# BMS.net
KiCad netlist of a schematic drawn in Altium Designer
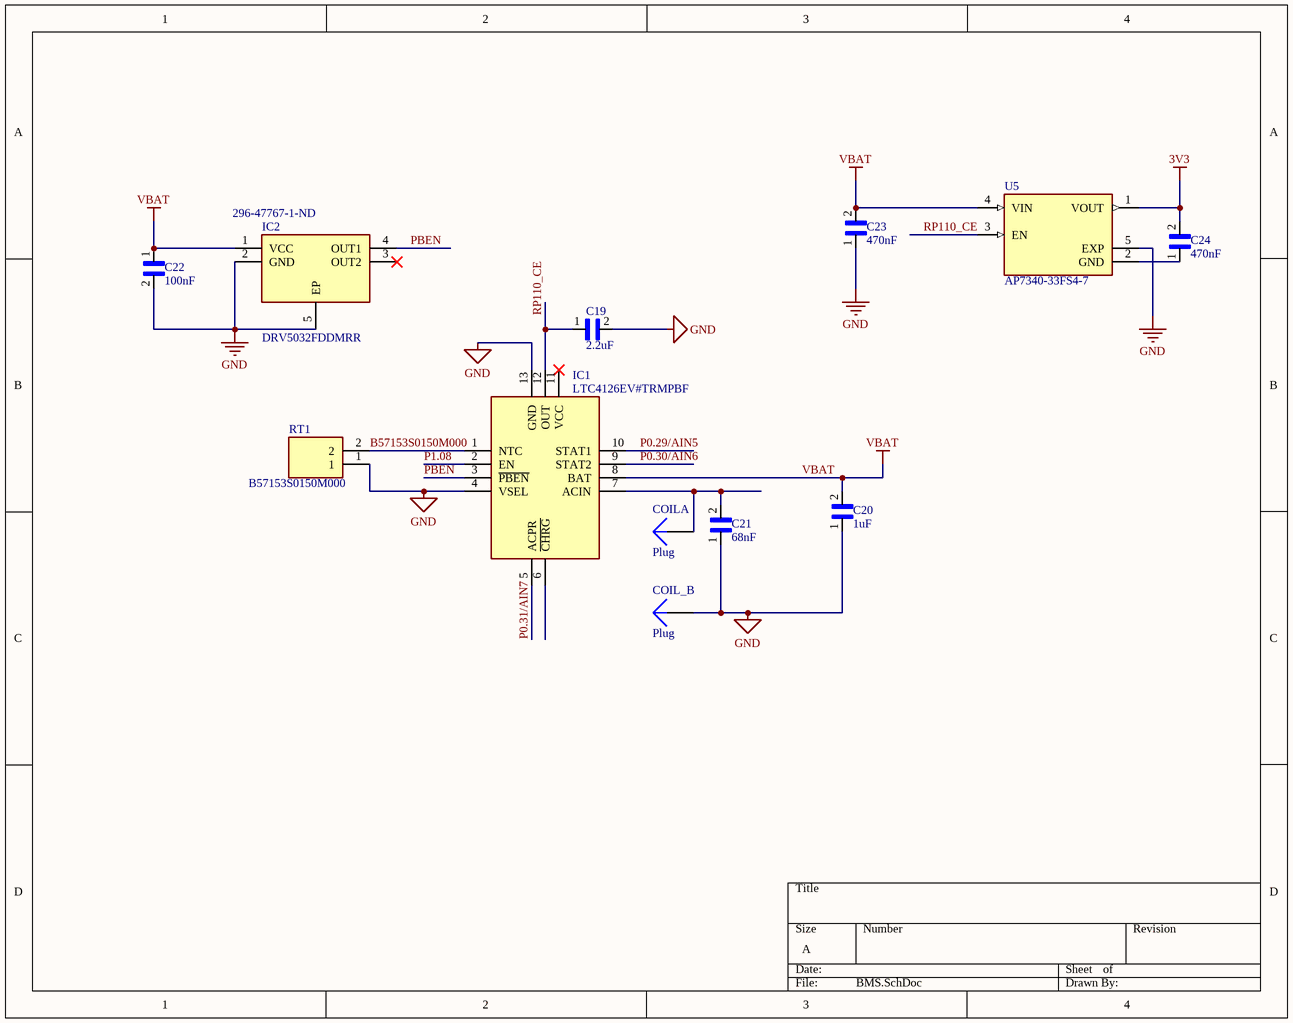
[diagram p0: BMS.SchDoc]

(export (version "E")
  (design (tool "Eeschema 10.0.6"))
  (components
    (comp (ref "C19")
      (value "2.2uF")
      (footprint "CAPC1005X55N")
      (description "Cap Ceramic 2.2uF 16V X5R 20% SMD 0402 85C Paper T/R")
      (fields
        (field (name "MANUFACTURER") "TDK")
        (field (name "MANUFACTURER PART NUMBER") "C1005X5R1C225M050BC")
      )
      (libsource (lib "Flex PCB") (part "C1005X5R1C225M050BC"))
    )
    (comp (ref "C20")
      (value "1uF")
      (footprint "CAPC1005X56N")
      (description "0402 1 uF 16 V ±10 % Tolerance X5R Surface Mount Multilayer Ceramic Capacitor")
      (fields
        (field (name "MANUFACTURER") "Kyocera AVX")
        (field (name "MANUFACTURER PART NUMBER") "0402YD105KAT2A")
      )
      (libsource (lib "SnapEDA_Library") (part "0402YD105KAT2A"))
    )
    (comp (ref "C21")
      (value "68nF")
      (footprint "CAPC1608X90N")
      (description "0603 68 nF 16 V ±5 % Tolerance X7R Surface Mount Multilayer Ceramic Capacitor")
      (fields
        (field (name "MANUFACTURER") "Kyocera AVX")
        (field (name "MANUFACTURER PART NUMBER") "0603YC683JAT2A")
      )
      (libsource (lib "SnapEDA_Library") (part "0603YC683JAT2A"))
    )
    (comp (ref "C22")
      (value "100nF")
      (footprint "CAPC1005X55N")
      (description "Cap Ceramic 0.1uF 10V X7R 10% Pad SMD 0402 125C T/R")
      (fields
        (field (name "MANUFACTURER") "Samsung")
        (field (name "MANUFACTURER PART NUMBER") "CL05B104KP5NNNC")
      )
      (libsource (lib "SnapEDA_Library") (part "CL05B104KP5NNNC"))
    )
    (comp (ref "C23")
      (value "470nF")
      (footprint "CAPC0603X33N")
      (description "Cap Ceramic 0.47uF 6.3V X5R 10% SMD 0201 85C Paper T/R")
      (fields
        (field (name "MANUFACTURER") "Kyocera AVX")
        (field (name "MANUFACTURER PART NUMBER") "02016D474KAT2A")
      )
      (libsource (lib "SnapEDA_Library") (part "02016D474KAT2A"))
    )
    (comp (ref "C24")
      (value "470nF")
      (footprint "CAPC0603X33N")
      (description "Cap Ceramic 0.47uF 6.3V X5R 10% SMD 0201 85C Paper T/R")
      (fields
        (field (name "MANUFACTURER") "Kyocera AVX")
        (field (name "MANUFACTURER PART NUMBER") "02016D474KAT2A")
      )
      (libsource (lib "SnapEDA_Library") (part "02016D474KAT2A"))
    )
    (comp (ref "COILA")
      (value "Plug")
      (footprint "PIN1")
      (fields (field (name "PUBLISHER") "Altium Limited"))
      (libsource (lib "Miscellaneous Connectors") (part "Plug"))
    )
    (comp (ref "COIL_B")
      (value "Plug")
      (footprint "PIN1")
      (fields (field (name "PUBLISHER") "Altium Limited"))
      (libsource (lib "Miscellaneous Connectors") (part "Plug"))
    )
    (comp (ref "IC1")
      (value "LTC4126EV#TRMPBF")
      (footprint "QFN50P200X200X83-13N-D")
      (description "Linear Battery Charger Li-Ion 7.5mA 4.2V/4.35V 12-Pin LQFN EP T/R")
      (fields
        (field (name "MANUFACTURER") "Analog Devices / Linear Technology")
        (field (name "MANUFACTURER PART NUMBER") "LTC4126EV#TRPBF")
      )
      (libsource (lib "Flex PCB") (part "LTC4126EV#TRMPBF"))
    )
    (comp (ref "IC2")
      (value "DRV5032FDDMRR")
      (footprint "SamacSys:SON50P140X110X40-5N")
      (description "Low power (5 Hz, <1µA), low voltage (up to 5.5V) switch 4-X2SON -40 to 85")
      (fields
        (field (name "SUPPLIER PART NUMBER 1") "296-47767-1-ND")
        (field (name "MANUFACTURER") "Texas Instruments")
      )
      (libsource (lib "*") (part "DRV5032FDDMRR"))
    )
    (comp (ref "RT1")
      (value "B57153S0150M000")
      (description "Inrush current limiters include PTC and NTC Thermistors.")
      (fields (field (name "MANUFACTURER") "TDK EPCOS") (field (name "TOLERANCE") "20%"))
      (libsource (lib "Flex PCB") (part "B57153S0150M000"))
    )
    (comp (ref "U5")
      (value "AP7340-33FS4-7")
      (footprint "VREG_AP7340-33FS4-7")
      (description "AP7340 Series 3.3 V Fixed Output 150 mA SMT LDO Regulator - DFN1010-4")
      (fields (field (name "MANUFACTURER") "Diodes"))
      (libsource (lib "SnapEDA_Library") (part "AP7340-33FS4-7"))
    )
  )
  (nets
    (net (code "1") (name "/B57153S0150M000") (class "Default")
      (node (ref "IC1") (pin "1") (pinfunction "NTC_1") (pintype "passive"))
      (node (ref "RT1") (pin "2") (pinfunction "2_2") (pintype "passive"))
    )
    (net (code "2") (name "/P0.29{slash}AIN5") (class "Default")
      (node (ref "IC1") (pin "10") (pinfunction "STAT1_10") (pintype "passive"))
    )
    (net (code "3") (name "/P0.30{slash}AIN6") (class "Default")
      (node (ref "IC1") (pin "9") (pinfunction "STAT2_9") (pintype "passive"))
    )
    (net (code "4") (name "/P0.31{slash}AIN7") (class "Default")
      (node (ref "IC1") (pin "5") (pinfunction "ACPR_5") (pintype "passive"))
    )
    (net (code "5") (name "/P1.08") (class "Default")
      (node (ref "IC1") (pin "2") (pinfunction "EN_2") (pintype "passive"))
    )
    (net (code "6") (name "/PBEN") (class "Default")
      (node (ref "IC1") (pin "3") (pinfunction "~{PBEN}_3") (pintype "passive"))
      (node (ref "IC2") (pin "4") (pinfunction "OUT1_4") (pintype "passive"))
    )
    (net (code "7") (name "/RP110_CE") (class "Default")
      (node (ref "C19") (pin "1") (pinfunction "1_1") (pintype "passive"))
      (node (ref "IC1") (pin "12") (pinfunction "OUT_12") (pintype "passive"))
      (node (ref "U5") (pin "3") (pinfunction "EN_3") (pintype "input"))
    )
    (net (code "8") (name "3V3") (class "Default")
      (node (ref "C24") (pin "2") (pinfunction "2_2") (pintype "passive"))
      (node (ref "U5") (pin "1") (pinfunction "VOUT_1") (pintype "output"))
    )
    (net (code "9") (name "GND") (class "Default")
      (node (ref "C19") (pin "2") (pinfunction "2_2") (pintype "passive"))
      (node (ref "C20") (pin "1") (pinfunction "1_1") (pintype "passive"))
      (node (ref "C21") (pin "1") (pinfunction "1_1") (pintype "passive"))
      (node (ref "C22") (pin "2") (pinfunction "2_2") (pintype "passive"))
      (node (ref "C23") (pin "1") (pinfunction "1_1") (pintype "passive"))
      (node (ref "COIL_B") (pin "1") (pinfunction "1_1") (pintype "passive"))
      (node (ref "IC1") (pin "13") (pinfunction "GND_13") (pintype "passive"))
      (node (ref "IC1") (pin "4") (pinfunction "VSEL_4") (pintype "passive"))
      (node (ref "IC2") (pin "2") (pinfunction "GND_2") (pintype "passive"))
      (node (ref "IC2") (pin "5") (pinfunction "EP_5") (pintype "passive"))
      (node (ref "RT1") (pin "1") (pinfunction "1_1") (pintype "passive"))
      (node (ref "U5") (pin "5") (pinfunction "EXP_5") (pintype "passive"))
    )
    (net (code "10") (name "Net-(IC1-ACIN)") (class "Default")
      (node (ref "C21") (pin "2") (pinfunction "2_2") (pintype "passive"))
      (node (ref "COILA") (pin "1") (pinfunction "1_1") (pintype "passive"))
      (node (ref "IC1") (pin "7") (pinfunction "ACIN_7") (pintype "passive"))
    )
    (net (code "11") (name "Net-(U5-GND)") (class "Default")
      (node (ref "C24") (pin "1") (pinfunction "1_1") (pintype "passive"))
      (node (ref "U5") (pin "2") (pinfunction "GND_2") (pintype "power_in"))
    )
    (net (code "12") (name "VBAT") (class "Default")
      (node (ref "C20") (pin "2") (pinfunction "2_2") (pintype "passive"))
      (node (ref "C22") (pin "1") (pinfunction "1_1") (pintype "passive"))
      (node (ref "C23") (pin "2") (pinfunction "2_2") (pintype "passive"))
      (node (ref "IC1") (pin "8") (pinfunction "BAT_8") (pintype "passive"))
      (node (ref "IC2") (pin "1") (pinfunction "VCC_1") (pintype "passive"))
      (node (ref "U5") (pin "4") (pinfunction "VIN_4") (pintype "input"))
    )
    (net (code "13") (name "unconnected-(IC1-VCC-Pad11)") (class "Default")
      (node (ref "IC1") (pin "11") (pinfunction "VCC_11") (pintype "passive+no_connect"))
    )
    (net (code "14") (name "unconnected-(IC1-~{CHRG}-Pad6)") (class "Default")
      (node (ref "IC1") (pin "6") (pinfunction "~{CHRG}_6") (pintype "passive"))
    )
    (net (code "15") (name "unconnected-(IC2-OUT2-Pad3)") (class "Default")
      (node (ref "IC2") (pin "3") (pinfunction "OUT2_3") (pintype "passive+no_connect"))
    )
  )
)
